# IRQF103C8revB.net
KiCad netlist of a schematic drawn in EAGLE
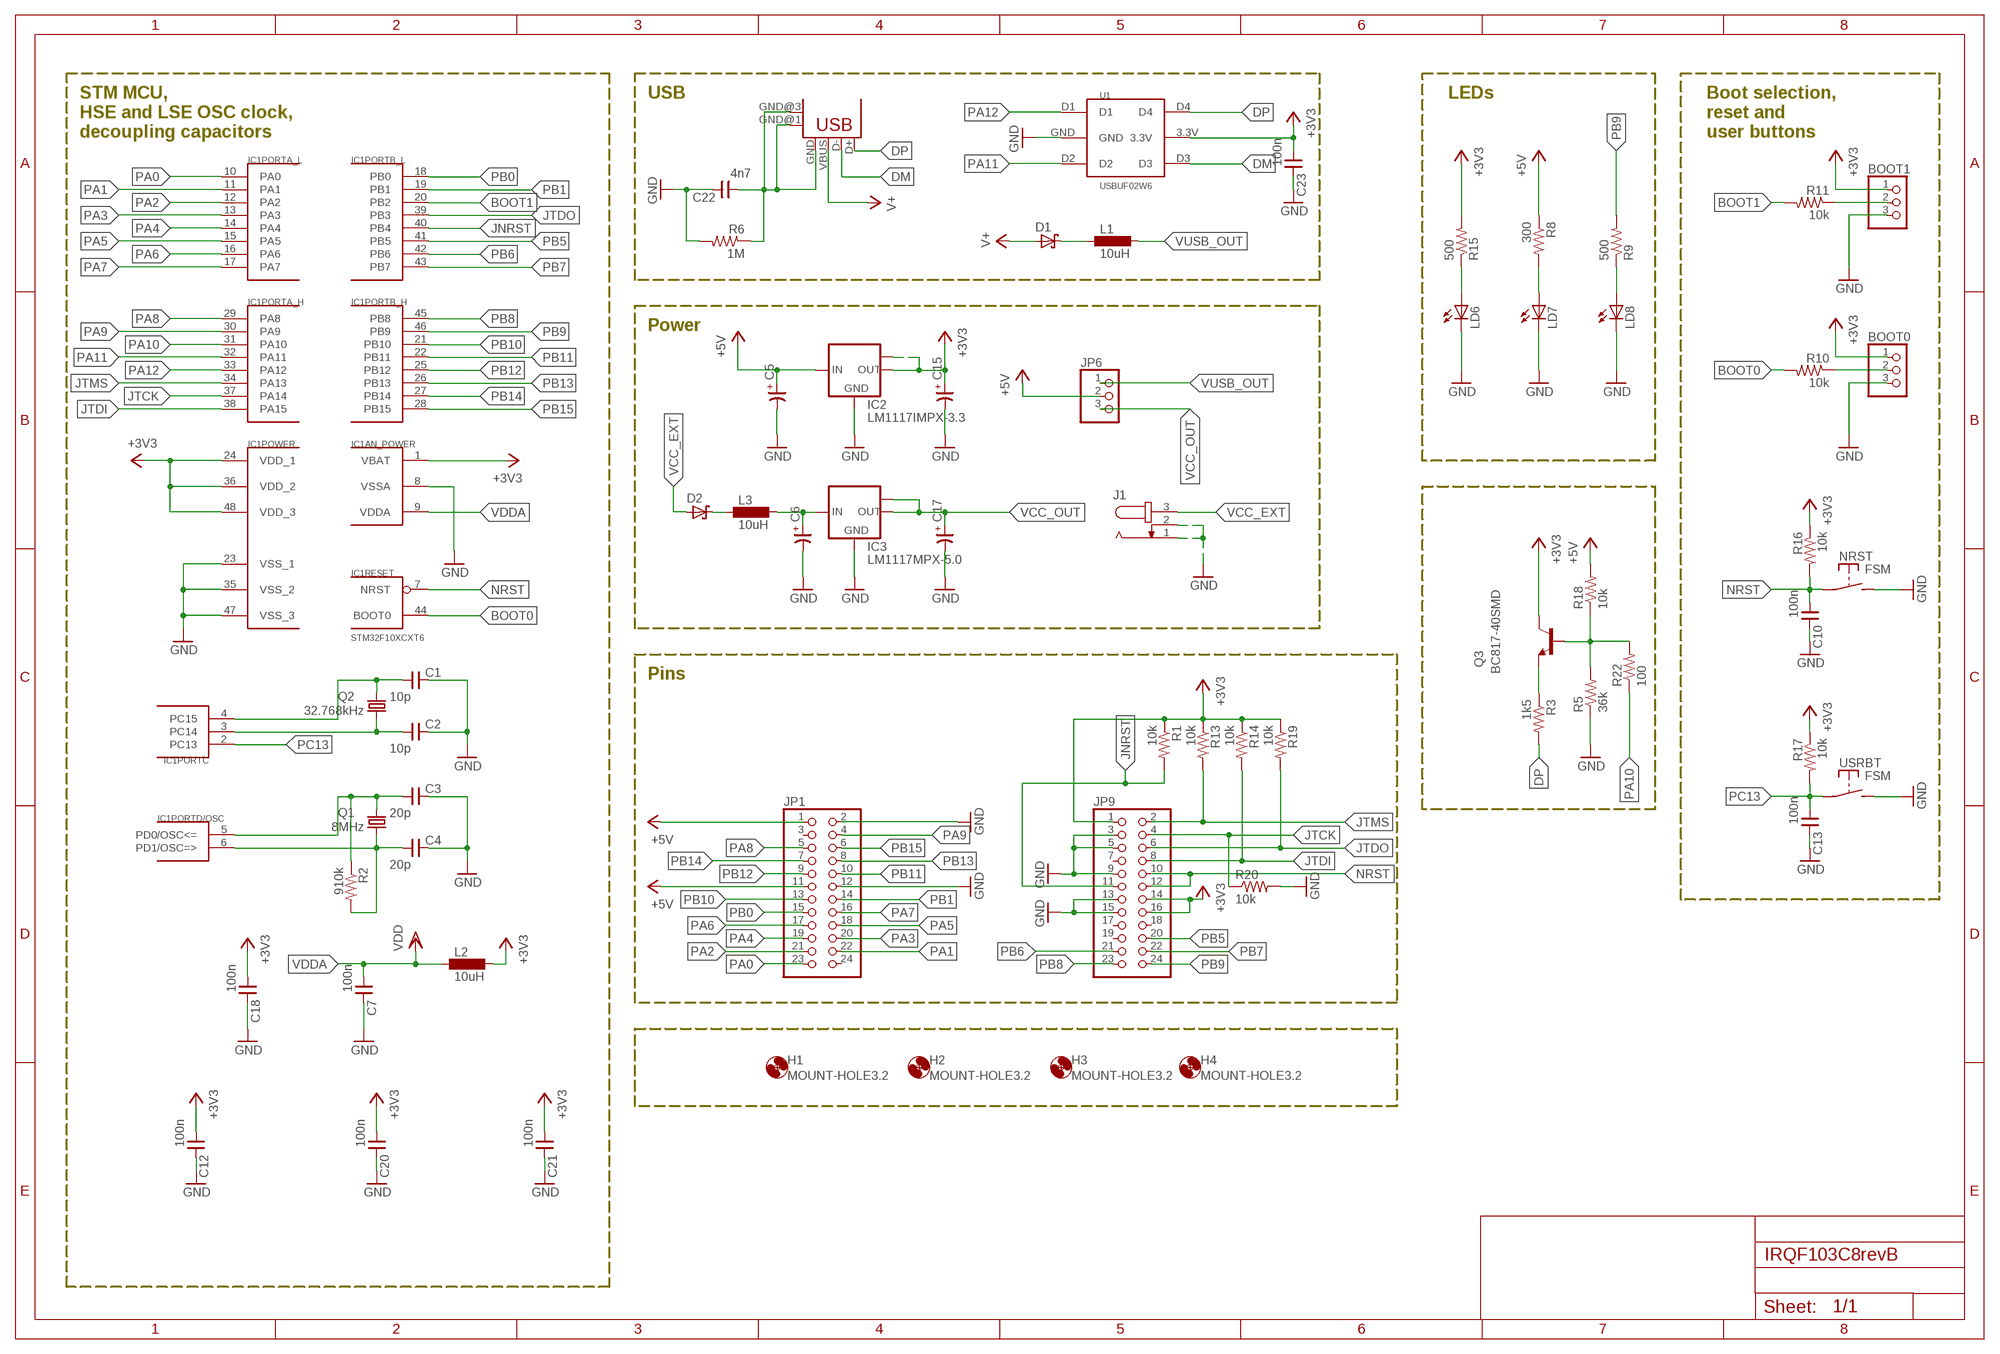
[diagram p0: schematic, sheet 1]

(export (version "E")
  (design (tool "Eeschema 10.0.6"))
  (components
    (comp (ref "BOOT0")
      (value "PINHD-1X3")
      (footprint "eagle-import:1X03")
      (libsource (lib "eagle-import") (part "PINHD-1X3"))
    )
    (comp (ref "BOOT1")
      (value "PINHD-1X3")
      (footprint "eagle-import:1X03")
      (libsource (lib "eagle-import") (part "PINHD-1X3"))
    )
    (comp (ref "C1")
      (value "10p")
      (footprint "eagle-import:0805")
      (libsource (lib "eagle-import") (part "CNP-0805"))
    )
    (comp (ref "C2")
      (value "10p")
      (footprint "eagle-import:0805")
      (libsource (lib "eagle-import") (part "CNP-0805"))
    )
    (comp (ref "C3")
      (value "20p")
      (footprint "eagle-import:0805")
      (libsource (lib "eagle-import") (part "CNP-0805"))
    )
    (comp (ref "C4")
      (value "20p")
      (footprint "eagle-import:0805")
      (libsource (lib "eagle-import") (part "CNP-0805"))
    )
    (comp (ref "C5")
      (value "CP-3258-TE-B")
      (footprint "eagle-import:3528-TE-B")
      (libsource (lib "eagle-import") (part "CP-3258-TE-B"))
    )
    (comp (ref "C6")
      (value "CP-3258-TE-B")
      (footprint "eagle-import:3528-TE-B")
      (libsource (lib "eagle-import") (part "CP-3258-TE-B"))
    )
    (comp (ref "C7")
      (value "100n")
      (footprint "eagle-import:0805")
      (libsource (lib "eagle-import") (part "CNP-0805"))
    )
    (comp (ref "C10")
      (value "100n")
      (footprint "eagle-import:0805")
      (libsource (lib "eagle-import") (part "CNP-0805"))
    )
    (comp (ref "C12")
      (value "100n")
      (footprint "eagle-import:0805")
      (libsource (lib "eagle-import") (part "CNP-0805"))
    )
    (comp (ref "C13")
      (value "100n")
      (footprint "eagle-import:0805")
      (libsource (lib "eagle-import") (part "CNP-0805"))
    )
    (comp (ref "C15")
      (value "CP-3216-TE-A")
      (footprint "eagle-import:3216-TE-A")
      (libsource (lib "eagle-import") (part "CP-3216-TE-A"))
    )
    (comp (ref "C17")
      (value "CP-3216-TE-A")
      (footprint "eagle-import:3216-TE-A")
      (libsource (lib "eagle-import") (part "CP-3216-TE-A"))
    )
    (comp (ref "C18")
      (value "100n")
      (footprint "eagle-import:0805")
      (libsource (lib "eagle-import") (part "CNP-0805"))
    )
    (comp (ref "C20")
      (value "100n")
      (footprint "eagle-import:0805")
      (libsource (lib "eagle-import") (part "CNP-0805"))
    )
    (comp (ref "C21")
      (value "100n")
      (footprint "eagle-import:0805")
      (libsource (lib "eagle-import") (part "CNP-0805"))
    )
    (comp (ref "C22")
      (value "4n7")
      (footprint "eagle-import:0805")
      (libsource (lib "eagle-import") (part "CNP-0805"))
    )
    (comp (ref "C23")
      (value "100n")
      (footprint "eagle-import:0805")
      (libsource (lib "eagle-import") (part "CNP-0805"))
    )
    (comp (ref "D1")
      (value "SCHOTTKY_SMA")
      (footprint "eagle-import:DIOM5326X292N")
      (libsource (lib "eagle-import") (part "SCHOTTKY_SMA"))
    )
    (comp (ref "D2")
      (value "SCHOTTKY_SMA")
      (footprint "eagle-import:DIOM5326X292N")
      (libsource (lib "eagle-import") (part "SCHOTTKY_SMA"))
    )
    (comp (ref "H1")
      (value "MOUNT-HOLE3.2")
      (footprint "eagle-import:3,2")
      (libsource (lib "eagle-import") (part "MOUNT-HOLE3.2"))
    )
    (comp (ref "H2")
      (value "MOUNT-HOLE3.2")
      (footprint "eagle-import:3,2")
      (libsource (lib "eagle-import") (part "MOUNT-HOLE3.2"))
    )
    (comp (ref "H3")
      (value "MOUNT-HOLE3.2")
      (footprint "eagle-import:3,2")
      (libsource (lib "eagle-import") (part "MOUNT-HOLE3.2"))
    )
    (comp (ref "H4")
      (value "MOUNT-HOLE3.2")
      (footprint "eagle-import:3,2")
      (libsource (lib "eagle-import") (part "MOUNT-HOLE3.2"))
    )
    (comp (ref "IC1")
      (value "STM32F10XCXT6")
      (footprint "eagle-import:TQFP48")
      (libsource (lib "eagle-import") (part "STM32F10XCXT6"))
    )
    (comp (ref "IC2")
      (value "LM1117IMPX-3.3")
      (footprint "eagle-import:SOT223")
      (libsource (lib "eagle-import") (part "LM1117IMPX-3.3"))
    )
    (comp (ref "IC3")
      (value "LM1117MPX-5.0")
      (footprint "eagle-import:SOT223")
      (libsource (lib "eagle-import") (part "LM1117MPX-5.0"))
    )
    (comp (ref "J1")
      (value "JACK-PLUG1")
      (footprint "eagle-import:SPC4078")
      (libsource (lib "eagle-import") (part "JACK-PLUG1"))
    )
    (comp (ref "JP1")
      (value "PINHD-2X12")
      (footprint "eagle-import:2X12")
      (libsource (lib "eagle-import") (part "PINHD-2X12"))
    )
    (comp (ref "JP6")
      (value "PINHD-1X3")
      (footprint "eagle-import:1X03")
      (libsource (lib "eagle-import") (part "PINHD-1X3"))
    )
    (comp (ref "JP9")
      (value "PINHD-2X12")
      (footprint "eagle-import:2X12")
      (libsource (lib "eagle-import") (part "PINHD-2X12"))
    )
    (comp (ref "L1")
      (value "10uH")
      (footprint "eagle-import:INDC1608X95N")
      (libsource (lib "eagle-import") (part "INDUCTOR_0603"))
    )
    (comp (ref "L2")
      (value "10uH")
      (footprint "eagle-import:INDC1608X95N")
      (libsource (lib "eagle-import") (part "INDUCTOR_0603"))
    )
    (comp (ref "L3")
      (value "10uH")
      (footprint "eagle-import:INDC1608X95N")
      (libsource (lib "eagle-import") (part "INDUCTOR_0603"))
    )
    (comp (ref "LD6")
      (value "LEDCHIPLED_0805")
      (footprint "eagle-import:CHIPLED_0805")
      (libsource (lib "eagle-import") (part "LEDCHIPLED_0805"))
    )
    (comp (ref "LD7")
      (value "LEDCHIPLED_0805")
      (footprint "eagle-import:CHIPLED_0805")
      (libsource (lib "eagle-import") (part "LEDCHIPLED_0805"))
    )
    (comp (ref "LD8")
      (value "LEDCHIPLED_0805")
      (footprint "eagle-import:CHIPLED_0805")
      (libsource (lib "eagle-import") (part "LEDCHIPLED_0805"))
    )
    (comp (ref "NRST")
      (value "FSM")
      (footprint "eagle-import:FSM")
      (libsource (lib "eagle-import") (part "FSM"))
    )
    (comp (ref "Q1")
      (value "8MHz")
      (footprint "eagle-import:HC49_S")
      (libsource (lib "eagle-import") (part "CRYTALHC49S"))
    )
    (comp (ref "Q2")
      (value "32.768kHz")
      (footprint "eagle-import:TC26H")
      (libsource (lib "eagle-import") (part "CRYTALTC26H"))
    )
    (comp (ref "Q3")
      (value "BC817-40SMD")
      (footprint "eagle-import:SOT23-BEC")
      (libsource (lib "eagle-import") (part "BC817SMD-40"))
    )
    (comp (ref "R1")
      (value "10k")
      (footprint "eagle-import:M0805")
      (libsource (lib "eagle-import") (part "R-US_M0805"))
    )
    (comp (ref "R2")
      (value "910k")
      (footprint "eagle-import:M0805")
      (libsource (lib "eagle-import") (part "R-US_M0805"))
    )
    (comp (ref "R3")
      (value "1k5")
      (footprint "eagle-import:M0805")
      (libsource (lib "eagle-import") (part "R-US_M0805"))
    )
    (comp (ref "R5")
      (value "36k")
      (footprint "eagle-import:M0805")
      (libsource (lib "eagle-import") (part "R-US_M0805"))
    )
    (comp (ref "R6")
      (value "1M")
      (footprint "eagle-import:M0805")
      (libsource (lib "eagle-import") (part "R-US_M0805"))
    )
    (comp (ref "R8")
      (value "300")
      (footprint "eagle-import:M0805")
      (libsource (lib "eagle-import") (part "R-US_M0805"))
    )
    (comp (ref "R9")
      (value "500")
      (footprint "eagle-import:M0805")
      (libsource (lib "eagle-import") (part "R-US_M0805"))
    )
    (comp (ref "R10")
      (value "10k")
      (footprint "eagle-import:M0805")
      (libsource (lib "eagle-import") (part "R-US_M0805"))
    )
    (comp (ref "R11")
      (value "10k")
      (footprint "eagle-import:M0805")
      (libsource (lib "eagle-import") (part "R-US_M0805"))
    )
    (comp (ref "R13")
      (value "10k")
      (footprint "eagle-import:M0805")
      (libsource (lib "eagle-import") (part "R-US_M0805"))
    )
    (comp (ref "R14")
      (value "10k")
      (footprint "eagle-import:M0805")
      (libsource (lib "eagle-import") (part "R-US_M0805"))
    )
    (comp (ref "R15")
      (value "500")
      (footprint "eagle-import:M0805")
      (libsource (lib "eagle-import") (part "R-US_M0805"))
    )
    (comp (ref "R16")
      (value "10k")
      (footprint "eagle-import:M0805")
      (libsource (lib "eagle-import") (part "R-US_M0805"))
    )
    (comp (ref "R17")
      (value "10k")
      (footprint "eagle-import:M0805")
      (libsource (lib "eagle-import") (part "R-US_M0805"))
    )
    (comp (ref "R18")
      (value "10k")
      (footprint "eagle-import:M0805")
      (libsource (lib "eagle-import") (part "R-US_M0805"))
    )
    (comp (ref "R19")
      (value "10k")
      (footprint "eagle-import:M0805")
      (libsource (lib "eagle-import") (part "R-US_M0805"))
    )
    (comp (ref "R20")
      (value "10k")
      (footprint "eagle-import:M0805")
      (libsource (lib "eagle-import") (part "R-US_M0805"))
    )
    (comp (ref "R22")
      (value "100")
      (footprint "eagle-import:M0805")
      (libsource (lib "eagle-import") (part "R-US_M0805"))
    )
    (comp (ref "U1")
      (value "USBUF02W6")
      (footprint "eagle-import:SOT23-6L")
      (libsource (lib "eagle-import") (part "USBUF02W6"))
    )
    (comp (ref "USB1")
      (value "USB-MB-S")
      (footprint "eagle-import:USB-MB-S")
      (libsource (lib "eagle-import") (part "USB-MB-S"))
    )
    (comp (ref "USRBT")
      (value "FSM")
      (footprint "eagle-import:FSM")
      (libsource (lib "eagle-import") (part "FSM"))
    )
  )
  (nets
    (net (code "1") (name "+3V3") (class "Default")
      (node (ref "BOOT0") (pin "1") (pinfunction "1_1") (pintype "passive"))
      (node (ref "BOOT1") (pin "1") (pinfunction "1_1") (pintype "passive"))
      (node (ref "C12") (pin "1") (pinfunction "1_1") (pintype "passive"))
      (node (ref "C15") (pin "+") (pinfunction "+_+") (pintype "passive"))
      (node (ref "C18") (pin "1") (pinfunction "1_1") (pintype "passive"))
      (node (ref "C20") (pin "1") (pinfunction "1_1") (pintype "passive"))
      (node (ref "C21") (pin "1") (pinfunction "1_1") (pintype "passive"))
      (node (ref "C23") (pin "1") (pinfunction "1_1") (pintype "passive"))
      (node (ref "IC1") (pin "1") (pinfunction "VBAT_1") (pintype "power_in"))
      (node (ref "IC1") (pin "24") (pinfunction "VDD_1_24") (pintype "power_in"))
      (node (ref "IC1") (pin "36") (pinfunction "VDD_2_36") (pintype "power_in"))
      (node (ref "IC1") (pin "48") (pinfunction "VDD_3_48") (pintype "power_in"))
      (node (ref "IC2") (pin "2") (pinfunction "OUT_2") (pintype "passive"))
      (node (ref "IC2") (pin "TAB") (pinfunction "OUT1_TAB") (pintype "passive"))
      (node (ref "JP9") (pin "1") (pinfunction "1_1") (pintype "passive"))
      (node (ref "JP9") (pin "14") (pinfunction "14_14") (pintype "passive"))
      (node (ref "JP9") (pin "16") (pinfunction "16_16") (pintype "passive"))
      (node (ref "L2") (pin "2") (pinfunction "2_2") (pintype "passive"))
      (node (ref "Q3") (pin "C") (pinfunction "C_C") (pintype "passive"))
      (node (ref "R1") (pin "1") (pinfunction "1_1") (pintype "passive"))
      (node (ref "R13") (pin "1") (pinfunction "1_1") (pintype "passive"))
      (node (ref "R14") (pin "1") (pinfunction "1_1") (pintype "passive"))
      (node (ref "R15") (pin "2") (pinfunction "2_2") (pintype "passive"))
      (node (ref "R16") (pin "1") (pinfunction "1_1") (pintype "passive"))
      (node (ref "R17") (pin "1") (pinfunction "1_1") (pintype "passive"))
      (node (ref "R19") (pin "1") (pinfunction "1_1") (pintype "passive"))
      (node (ref "U1") (pin "3.3V") (pinfunction "3.3V_3.3V") (pintype "bidirectional"))
    )
    (net (code "2") (name "+5V") (class "Default")
      (node (ref "C5") (pin "+") (pinfunction "+_+") (pintype "passive"))
      (node (ref "IC2") (pin "3") (pinfunction "IN_3") (pintype "input"))
      (node (ref "JP1") (pin "1") (pinfunction "1_1") (pintype "passive"))
      (node (ref "JP1") (pin "11") (pinfunction "11_11") (pintype "passive"))
      (node (ref "JP6") (pin "2") (pinfunction "2_2") (pintype "passive"))
      (node (ref "R18") (pin "2") (pinfunction "2_2") (pintype "passive"))
      (node (ref "R8") (pin "1") (pinfunction "1_1") (pintype "passive"))
    )
    (net (code "3") (name "BOOT0") (class "Default")
      (node (ref "IC1") (pin "44") (pinfunction "BOOT0_44") (pintype "input"))
      (node (ref "R10") (pin "2") (pinfunction "2_2") (pintype "passive"))
    )
    (net (code "4") (name "BOOT1") (class "Default")
      (node (ref "IC1") (pin "20") (pinfunction "PB2_20") (pintype "bidirectional"))
      (node (ref "R11") (pin "2") (pinfunction "2_2") (pintype "passive"))
    )
    (net (code "5") (name "DM") (class "Default")
      (node (ref "U1") (pin "D3") (pinfunction "D3_D3") (pintype "bidirectional"))
      (node (ref "USB1") (pin "D-") (pinfunction "D-_D-") (pintype "bidirectional"))
    )
    (net (code "6") (name "DP") (class "Default")
      (node (ref "R3") (pin "2") (pinfunction "2_2") (pintype "passive"))
      (node (ref "U1") (pin "D4") (pinfunction "D4_D4") (pintype "bidirectional"))
      (node (ref "USB1") (pin "D+") (pinfunction "D+_D+") (pintype "bidirectional"))
    )
    (net (code "7") (name "GND") (class "Default")
      (node (ref "BOOT0") (pin "3") (pinfunction "3_3") (pintype "passive"))
      (node (ref "BOOT1") (pin "3") (pinfunction "3_3") (pintype "passive"))
      (node (ref "C1") (pin "2") (pinfunction "2_2") (pintype "passive"))
      (node (ref "C10") (pin "2") (pinfunction "2_2") (pintype "passive"))
      (node (ref "C12") (pin "2") (pinfunction "2_2") (pintype "passive"))
      (node (ref "C13") (pin "2") (pinfunction "2_2") (pintype "passive"))
      (node (ref "C15") (pin "-") (pinfunction "-_-") (pintype "passive"))
      (node (ref "C17") (pin "-") (pinfunction "-_-") (pintype "passive"))
      (node (ref "C18") (pin "2") (pinfunction "2_2") (pintype "passive"))
      (node (ref "C2") (pin "2") (pinfunction "2_2") (pintype "passive"))
      (node (ref "C20") (pin "2") (pinfunction "2_2") (pintype "passive"))
      (node (ref "C21") (pin "2") (pinfunction "2_2") (pintype "passive"))
      (node (ref "C22") (pin "2") (pinfunction "2_2") (pintype "passive"))
      (node (ref "C23") (pin "2") (pinfunction "2_2") (pintype "passive"))
      (node (ref "C3") (pin "2") (pinfunction "2_2") (pintype "passive"))
      (node (ref "C4") (pin "2") (pinfunction "2_2") (pintype "passive"))
      (node (ref "C5") (pin "-") (pinfunction "-_-") (pintype "passive"))
      (node (ref "C6") (pin "-") (pinfunction "-_-") (pintype "passive"))
      (node (ref "C7") (pin "2") (pinfunction "2_2") (pintype "passive"))
      (node (ref "IC1") (pin "23") (pinfunction "VSS_1_23") (pintype "power_in"))
      (node (ref "IC1") (pin "35") (pinfunction "VSS_2_35") (pintype "power_in"))
      (node (ref "IC1") (pin "47") (pinfunction "VSS_3_47") (pintype "power_in"))
      (node (ref "IC1") (pin "8") (pinfunction "VSSA_8") (pintype "power_in"))
      (node (ref "IC2") (pin "1") (pinfunction "GND_1") (pintype "input"))
      (node (ref "IC3") (pin "1") (pinfunction "GND_1") (pintype "input"))
      (node (ref "J1") (pin "1") (pinfunction "1_1") (pintype "passive"))
      (node (ref "J1") (pin "2") (pinfunction "2_2") (pintype "passive"))
      (node (ref "JP1") (pin "12") (pinfunction "12_12") (pintype "passive"))
      (node (ref "JP1") (pin "2") (pinfunction "2_2") (pintype "passive"))
      (node (ref "JP9") (pin "13") (pinfunction "13_13") (pintype "passive"))
      (node (ref "JP9") (pin "15") (pinfunction "15_15") (pintype "passive"))
      (node (ref "JP9") (pin "3") (pinfunction "3_3") (pintype "passive"))
      (node (ref "JP9") (pin "5") (pinfunction "5_5") (pintype "passive"))
      (node (ref "JP9") (pin "9") (pinfunction "9_9") (pintype "passive"))
      (node (ref "LD6") (pin "C") (pinfunction "C_C") (pintype "passive"))
      (node (ref "LD7") (pin "C") (pinfunction "C_C") (pintype "passive"))
      (node (ref "LD8") (pin "C") (pinfunction "C_C") (pintype "passive"))
      (node (ref "NRST") (pin "P$2") (pinfunction "S_P$2") (pintype "passive"))
      (node (ref "R20") (pin "2") (pinfunction "2_2") (pintype "passive"))
      (node (ref "R5") (pin "1") (pinfunction "1_1") (pintype "passive"))
      (node (ref "R6") (pin "2") (pinfunction "2_2") (pintype "passive"))
      (node (ref "U1") (pin "GND") (pinfunction "GND_GND") (pintype "bidirectional"))
      (node (ref "USRBT") (pin "P$2") (pinfunction "S_P$2") (pintype "passive"))
    )
    (net (code "8") (name "JNRST") (class "Default")
      (node (ref "IC1") (pin "40") (pinfunction "PB4_40") (pintype "bidirectional"))
      (node (ref "JP9") (pin "11") (pinfunction "11_11") (pintype "passive"))
      (node (ref "R1") (pin "2") (pinfunction "2_2") (pintype "passive"))
    )
    (net (code "9") (name "JTCK") (class "Default")
      (node (ref "IC1") (pin "37") (pinfunction "PA14_37") (pintype "bidirectional"))
      (node (ref "JP9") (pin "4") (pinfunction "4_4") (pintype "passive"))
      (node (ref "R20") (pin "1") (pinfunction "1_1") (pintype "passive"))
    )
    (net (code "10") (name "JTDI") (class "Default")
      (node (ref "IC1") (pin "38") (pinfunction "PA15_38") (pintype "bidirectional"))
      (node (ref "JP9") (pin "8") (pinfunction "8_8") (pintype "passive"))
      (node (ref "R14") (pin "2") (pinfunction "2_2") (pintype "passive"))
    )
    (net (code "11") (name "JTDO") (class "Default")
      (node (ref "IC1") (pin "39") (pinfunction "PB3_39") (pintype "bidirectional"))
      (node (ref "JP9") (pin "6") (pinfunction "6_6") (pintype "passive"))
      (node (ref "R19") (pin "2") (pinfunction "2_2") (pintype "passive"))
    )
    (net (code "12") (name "JTMS") (class "Default")
      (node (ref "IC1") (pin "34") (pinfunction "PA13_34") (pintype "bidirectional"))
      (node (ref "JP9") (pin "2") (pinfunction "2_2") (pintype "passive"))
      (node (ref "R13") (pin "2") (pinfunction "2_2") (pintype "passive"))
    )
    (net (code "13") (name "NRST") (class "Default")
      (node (ref "C10") (pin "1") (pinfunction "1_1") (pintype "passive"))
      (node (ref "IC1") (pin "7") (pinfunction "NRST_7") (pintype "input"))
      (node (ref "JP9") (pin "10") (pinfunction "10_10") (pintype "passive"))
      (node (ref "JP9") (pin "12") (pinfunction "12_12") (pintype "passive"))
      (node (ref "NRST") (pin "P$1") (pinfunction "P_P$1") (pintype "passive"))
      (node (ref "R16") (pin "2") (pinfunction "2_2") (pintype "passive"))
    )
    (net (code "14") (name "Net-(BOOT0-Pad2)") (class "Default")
      (node (ref "BOOT0") (pin "2") (pinfunction "2_2") (pintype "passive"))
      (node (ref "R10") (pin "1") (pinfunction "1_1") (pintype "passive"))
    )
    (net (code "15") (name "Net-(BOOT1-Pad2)") (class "Default")
      (node (ref "BOOT1") (pin "2") (pinfunction "2_2") (pintype "passive"))
      (node (ref "R11") (pin "1") (pinfunction "1_1") (pintype "passive"))
    )
    (net (code "16") (name "Net-(C22-Pad1)") (class "Default")
      (node (ref "C22") (pin "1") (pinfunction "1_1") (pintype "passive"))
      (node (ref "R6") (pin "1") (pinfunction "1_1") (pintype "passive"))
      (node (ref "USB1") (pin "GND") (pinfunction "GND_GND") (pintype "bidirectional"))
      (node (ref "USB1") (pin "GND@1") (pinfunction "GND_GND@1") (pintype "bidirectional"))
      (node (ref "USB1") (pin "GND@3") (pinfunction "GND_GND@3") (pintype "bidirectional"))
    )
    (net (code "17") (name "Net-(D1-PadK)") (class "Default")
      (node (ref "D1") (pin "K") (pinfunction "K_K") (pintype "passive"))
      (node (ref "L1") (pin "1") (pinfunction "1_1") (pintype "passive"))
    )
    (net (code "18") (name "Net-(D2-PadK)") (class "Default")
      (node (ref "D2") (pin "K") (pinfunction "K_K") (pintype "passive"))
      (node (ref "L3") (pin "1") (pinfunction "1_1") (pintype "passive"))
    )
    (net (code "19") (name "Net-(IC1F-PC14)") (class "Default")
      (node (ref "C2") (pin "1") (pinfunction "1_1") (pintype "passive"))
      (node (ref "IC1") (pin "3") (pinfunction "PC14_3") (pintype "bidirectional"))
      (node (ref "Q2") (pin "1") (pinfunction "1_1") (pintype "passive"))
    )
    (net (code "20") (name "Net-(IC1F-PC15)") (class "Default")
      (node (ref "C1") (pin "1") (pinfunction "1_1") (pintype "passive"))
      (node (ref "IC1") (pin "4") (pinfunction "PC15_4") (pintype "bidirectional"))
      (node (ref "Q2") (pin "2") (pinfunction "2_2") (pintype "passive"))
    )
    (net (code "21") (name "Net-(IC1G-PD0{slash}OSC<=)") (class "Default")
      (node (ref "C3") (pin "1") (pinfunction "1_1") (pintype "passive"))
      (node (ref "IC1") (pin "5") (pinfunction "PD0/OSC<=_5") (pintype "bidirectional"))
      (node (ref "Q1") (pin "2") (pinfunction "2_2") (pintype "passive"))
      (node (ref "R2") (pin "1") (pinfunction "1_1") (pintype "passive"))
    )
    (net (code "22") (name "Net-(IC1G-PD1{slash}OSC=>)") (class "Default")
      (node (ref "C4") (pin "1") (pinfunction "1_1") (pintype "passive"))
      (node (ref "IC1") (pin "6") (pinfunction "PD1/OSC=>_6") (pintype "bidirectional"))
      (node (ref "Q1") (pin "1") (pinfunction "1_1") (pintype "passive"))
      (node (ref "R2") (pin "2") (pinfunction "2_2") (pintype "passive"))
    )
    (net (code "23") (name "Net-(IC3-IN)") (class "Default")
      (node (ref "C6") (pin "+") (pinfunction "+_+") (pintype "passive"))
      (node (ref "IC3") (pin "3") (pinfunction "IN_3") (pintype "input"))
      (node (ref "L3") (pin "2") (pinfunction "2_2") (pintype "passive"))
    )
    (net (code "24") (name "Net-(LD6-PadA)") (class "Default")
      (node (ref "LD6") (pin "A") (pinfunction "A_A") (pintype "passive"))
      (node (ref "R15") (pin "1") (pinfunction "1_1") (pintype "passive"))
    )
    (net (code "25") (name "Net-(LD7-PadA)") (class "Default")
      (node (ref "LD7") (pin "A") (pinfunction "A_A") (pintype "passive"))
      (node (ref "R8") (pin "2") (pinfunction "2_2") (pintype "passive"))
    )
    (net (code "26") (name "Net-(LD8-PadA)") (class "Default")
      (node (ref "LD8") (pin "A") (pinfunction "A_A") (pintype "passive"))
      (node (ref "R9") (pin "1") (pinfunction "1_1") (pintype "passive"))
    )
    (net (code "27") (name "Net-(Q3-PadB)") (class "Default")
      (node (ref "Q3") (pin "B") (pinfunction "B_B") (pintype "passive"))
      (node (ref "R18") (pin "1") (pinfunction "1_1") (pintype "passive"))
      (node (ref "R22") (pin "2") (pinfunction "2_2") (pintype "passive"))
      (node (ref "R5") (pin "2") (pinfunction "2_2") (pintype "passive"))
    )
    (net (code "28") (name "Net-(Q3-PadE)") (class "Default")
      (node (ref "Q3") (pin "E") (pinfunction "E_E") (pintype "passive"))
      (node (ref "R3") (pin "1") (pinfunction "1_1") (pintype "passive"))
    )
    (net (code "29") (name "PA0") (class "Default")
      (node (ref "IC1") (pin "10") (pinfunction "PA0_10") (pintype "bidirectional"))
      (node (ref "JP1") (pin "23") (pinfunction "23_23") (pintype "passive"))
    )
    (net (code "30") (name "PA1") (class "Default")
      (node (ref "IC1") (pin "11") (pinfunction "PA1_11") (pintype "bidirectional"))
      (node (ref "JP1") (pin "22") (pinfunction "22_22") (pintype "passive"))
    )
    (net (code "31") (name "PA2") (class "Default")
      (node (ref "IC1") (pin "12") (pinfunction "PA2_12") (pintype "bidirectional"))
      (node (ref "JP1") (pin "21") (pinfunction "21_21") (pintype "passive"))
    )
    (net (code "32") (name "PA3") (class "Default")
      (node (ref "IC1") (pin "13") (pinfunction "PA3_13") (pintype "bidirectional"))
      (node (ref "JP1") (pin "20") (pinfunction "20_20") (pintype "passive"))
    )
    (net (code "33") (name "PA4") (class "Default")
      (node (ref "IC1") (pin "14") (pinfunction "PA4_14") (pintype "bidirectional"))
      (node (ref "JP1") (pin "19") (pinfunction "19_19") (pintype "passive"))
    )
    (net (code "34") (name "PA5") (class "Default")
      (node (ref "IC1") (pin "15") (pinfunction "PA5_15") (pintype "bidirectional"))
      (node (ref "JP1") (pin "18") (pinfunction "18_18") (pintype "passive"))
    )
    (net (code "35") (name "PA6") (class "Default")
      (node (ref "IC1") (pin "16") (pinfunction "PA6_16") (pintype "bidirectional"))
      (node (ref "JP1") (pin "17") (pinfunction "17_17") (pintype "passive"))
    )
    (net (code "36") (name "PA7") (class "Default")
      (node (ref "IC1") (pin "17") (pinfunction "PA7_17") (pintype "bidirectional"))
      (node (ref "JP1") (pin "16") (pinfunction "16_16") (pintype "passive"))
    )
    (net (code "37") (name "PA8") (class "Default")
      (node (ref "IC1") (pin "29") (pinfunction "PA8_29") (pintype "bidirectional"))
      (node (ref "JP1") (pin "5") (pinfunction "5_5") (pintype "passive"))
    )
    (net (code "38") (name "PA9") (class "Default")
      (node (ref "IC1") (pin "30") (pinfunction "PA9_30") (pintype "bidirectional"))
      (node (ref "JP1") (pin "4") (pinfunction "4_4") (pintype "passive"))
    )
    (net (code "39") (name "PA10") (class "Default")
      (node (ref "IC1") (pin "31") (pinfunction "PA10_31") (pintype "bidirectional"))
      (node (ref "R22") (pin "1") (pinfunction "1_1") (pintype "passive"))
    )
    (net (code "40") (name "PA11") (class "Default")
      (node (ref "IC1") (pin "32") (pinfunction "PA11_32") (pintype "bidirectional"))
      (node (ref "U1") (pin "D2") (pinfunction "D2_D2") (pintype "bidirectional"))
    )
    (net (code "41") (name "PA12") (class "Default")
      (node (ref "IC1") (pin "33") (pinfunction "PA12_33") (pintype "bidirectional"))
      (node (ref "U1") (pin "D1") (pinfunction "D1_D1") (pintype "bidirectional"))
    )
    (net (code "42") (name "PB0") (class "Default")
      (node (ref "IC1") (pin "18") (pinfunction "PB0_18") (pintype "bidirectional"))
      (node (ref "JP1") (pin "15") (pinfunction "15_15") (pintype "passive"))
    )
    (net (code "43") (name "PB1") (class "Default")
      (node (ref "IC1") (pin "19") (pinfunction "PB1_19") (pintype "bidirectional"))
      (node (ref "JP1") (pin "14") (pinfunction "14_14") (pintype "passive"))
    )
    (net (code "44") (name "PB5") (class "Default")
      (node (ref "IC1") (pin "41") (pinfunction "PB5_41") (pintype "bidirectional"))
      (node (ref "JP9") (pin "20") (pinfunction "20_20") (pintype "passive"))
    )
    (net (code "45") (name "PB6") (class "Default")
      (node (ref "IC1") (pin "42") (pinfunction "PB6_42") (pintype "bidirectional"))
      (node (ref "JP9") (pin "21") (pinfunction "21_21") (pintype "passive"))
    )
    (net (code "46") (name "PB7") (class "Default")
      (node (ref "IC1") (pin "43") (pinfunction "PB7_43") (pintype "bidirectional"))
      (node (ref "JP9") (pin "22") (pinfunction "22_22") (pintype "passive"))
    )
    (net (code "47") (name "PB8") (class "Default")
      (node (ref "IC1") (pin "45") (pinfunction "PB8_45") (pintype "bidirectional"))
      (node (ref "JP9") (pin "23") (pinfunction "23_23") (pintype "passive"))
    )
    (net (code "48") (name "PB9") (class "Default")
      (node (ref "IC1") (pin "46") (pinfunction "PB9_46") (pintype "bidirectional"))
      (node (ref "JP9") (pin "24") (pinfunction "24_24") (pintype "passive"))
      (node (ref "R9") (pin "2") (pinfunction "2_2") (pintype "passive"))
    )
    (net (code "49") (name "PB10") (class "Default")
      (node (ref "IC1") (pin "21") (pinfunction "PB10_21") (pintype "bidirectional"))
      (node (ref "JP1") (pin "13") (pinfunction "13_13") (pintype "passive"))
    )
    (net (code "50") (name "PB11") (class "Default")
      (node (ref "IC1") (pin "22") (pinfunction "PB11_22") (pintype "bidirectional"))
      (node (ref "JP1") (pin "10") (pinfunction "10_10") (pintype "passive"))
    )
    (net (code "51") (name "PB12") (class "Default")
      (node (ref "IC1") (pin "25") (pinfunction "PB12_25") (pintype "bidirectional"))
      (node (ref "JP1") (pin "9") (pinfunction "9_9") (pintype "passive"))
    )
    (net (code "52") (name "PB13") (class "Default")
      (node (ref "IC1") (pin "26") (pinfunction "PB13_26") (pintype "bidirectional"))
      (node (ref "JP1") (pin "8") (pinfunction "8_8") (pintype "passive"))
    )
    (net (code "53") (name "PB14") (class "Default")
      (node (ref "IC1") (pin "27") (pinfunction "PB14_27") (pintype "bidirectional"))
      (node (ref "JP1") (pin "7") (pinfunction "7_7") (pintype "passive"))
    )
    (net (code "54") (name "PB15") (class "Default")
      (node (ref "IC1") (pin "28") (pinfunction "PB15_28") (pintype "bidirectional"))
      (node (ref "JP1") (pin "6") (pinfunction "6_6") (pintype "passive"))
    )
    (net (code "55") (name "PC13") (class "Default")
      (node (ref "C13") (pin "1") (pinfunction "1_1") (pintype "passive"))
      (node (ref "IC1") (pin "2") (pinfunction "PC13_2") (pintype "bidirectional"))
      (node (ref "R17") (pin "2") (pinfunction "2_2") (pintype "passive"))
      (node (ref "USRBT") (pin "P$1") (pinfunction "P_P$1") (pintype "passive"))
    )
    (net (code "56") (name "V+") (class "Default")
      (node (ref "D1") (pin "A") (pinfunction "A_A") (pintype "passive"))
      (node (ref "USB1") (pin "VBUS") (pinfunction "VBUS_VBUS") (pintype "bidirectional"))
    )
    (net (code "57") (name "VCC_EXT") (class "Default")
      (node (ref "D2") (pin "A") (pinfunction "A_A") (pintype "passive"))
      (node (ref "J1") (pin "3") (pinfunction "3_3") (pintype "passive"))
    )
    (net (code "58") (name "VCC_OUT") (class "Default")
      (node (ref "C17") (pin "+") (pinfunction "+_+") (pintype "passive"))
      (node (ref "IC3") (pin "2") (pinfunction "OUT_2") (pintype "passive"))
      (node (ref "IC3") (pin "TAB") (pinfunction "OUT1_TAB") (pintype "passive"))
      (node (ref "JP6") (pin "3") (pinfunction "3_3") (pintype "passive"))
    )
    (net (code "59") (name "VDDA") (class "Default")
      (node (ref "C7") (pin "1") (pinfunction "1_1") (pintype "passive"))
      (node (ref "IC1") (pin "9") (pinfunction "VDDA_9") (pintype "power_in"))
      (node (ref "L2") (pin "1") (pinfunction "1_1") (pintype "passive"))
    )
    (net (code "60") (name "VUSB_OUT") (class "Default")
      (node (ref "JP6") (pin "1") (pinfunction "1_1") (pintype "passive"))
      (node (ref "L1") (pin "2") (pinfunction "2_2") (pintype "passive"))
    )
    (net (code "61") (name "unconnected-(JP1-Pad3)") (class "Default")
      (node (ref "JP1") (pin "3") (pinfunction "3_3") (pintype "passive"))
    )
    (net (code "62") (name "unconnected-(JP1-Pad24)") (class "Default")
      (node (ref "JP1") (pin "24") (pinfunction "24_24") (pintype "passive"))
    )
    (net (code "63") (name "unconnected-(JP9-Pad7)") (class "Default")
      (node (ref "JP9") (pin "7") (pinfunction "7_7") (pintype "passive"))
    )
    (net (code "64") (name "unconnected-(JP9-Pad17)") (class "Default")
      (node (ref "JP9") (pin "17") (pinfunction "17_17") (pintype "passive"))
    )
    (net (code "65") (name "unconnected-(JP9-Pad18)") (class "Default")
      (node (ref "JP9") (pin "18") (pinfunction "18_18") (pintype "passive"))
    )
    (net (code "66") (name "unconnected-(JP9-Pad19)") (class "Default")
      (node (ref "JP9") (pin "19") (pinfunction "19_19") (pintype "passive"))
    )
  )
)
